# MultiboardV2.net
KiCad netlist of a schematic drawn in EAGLE
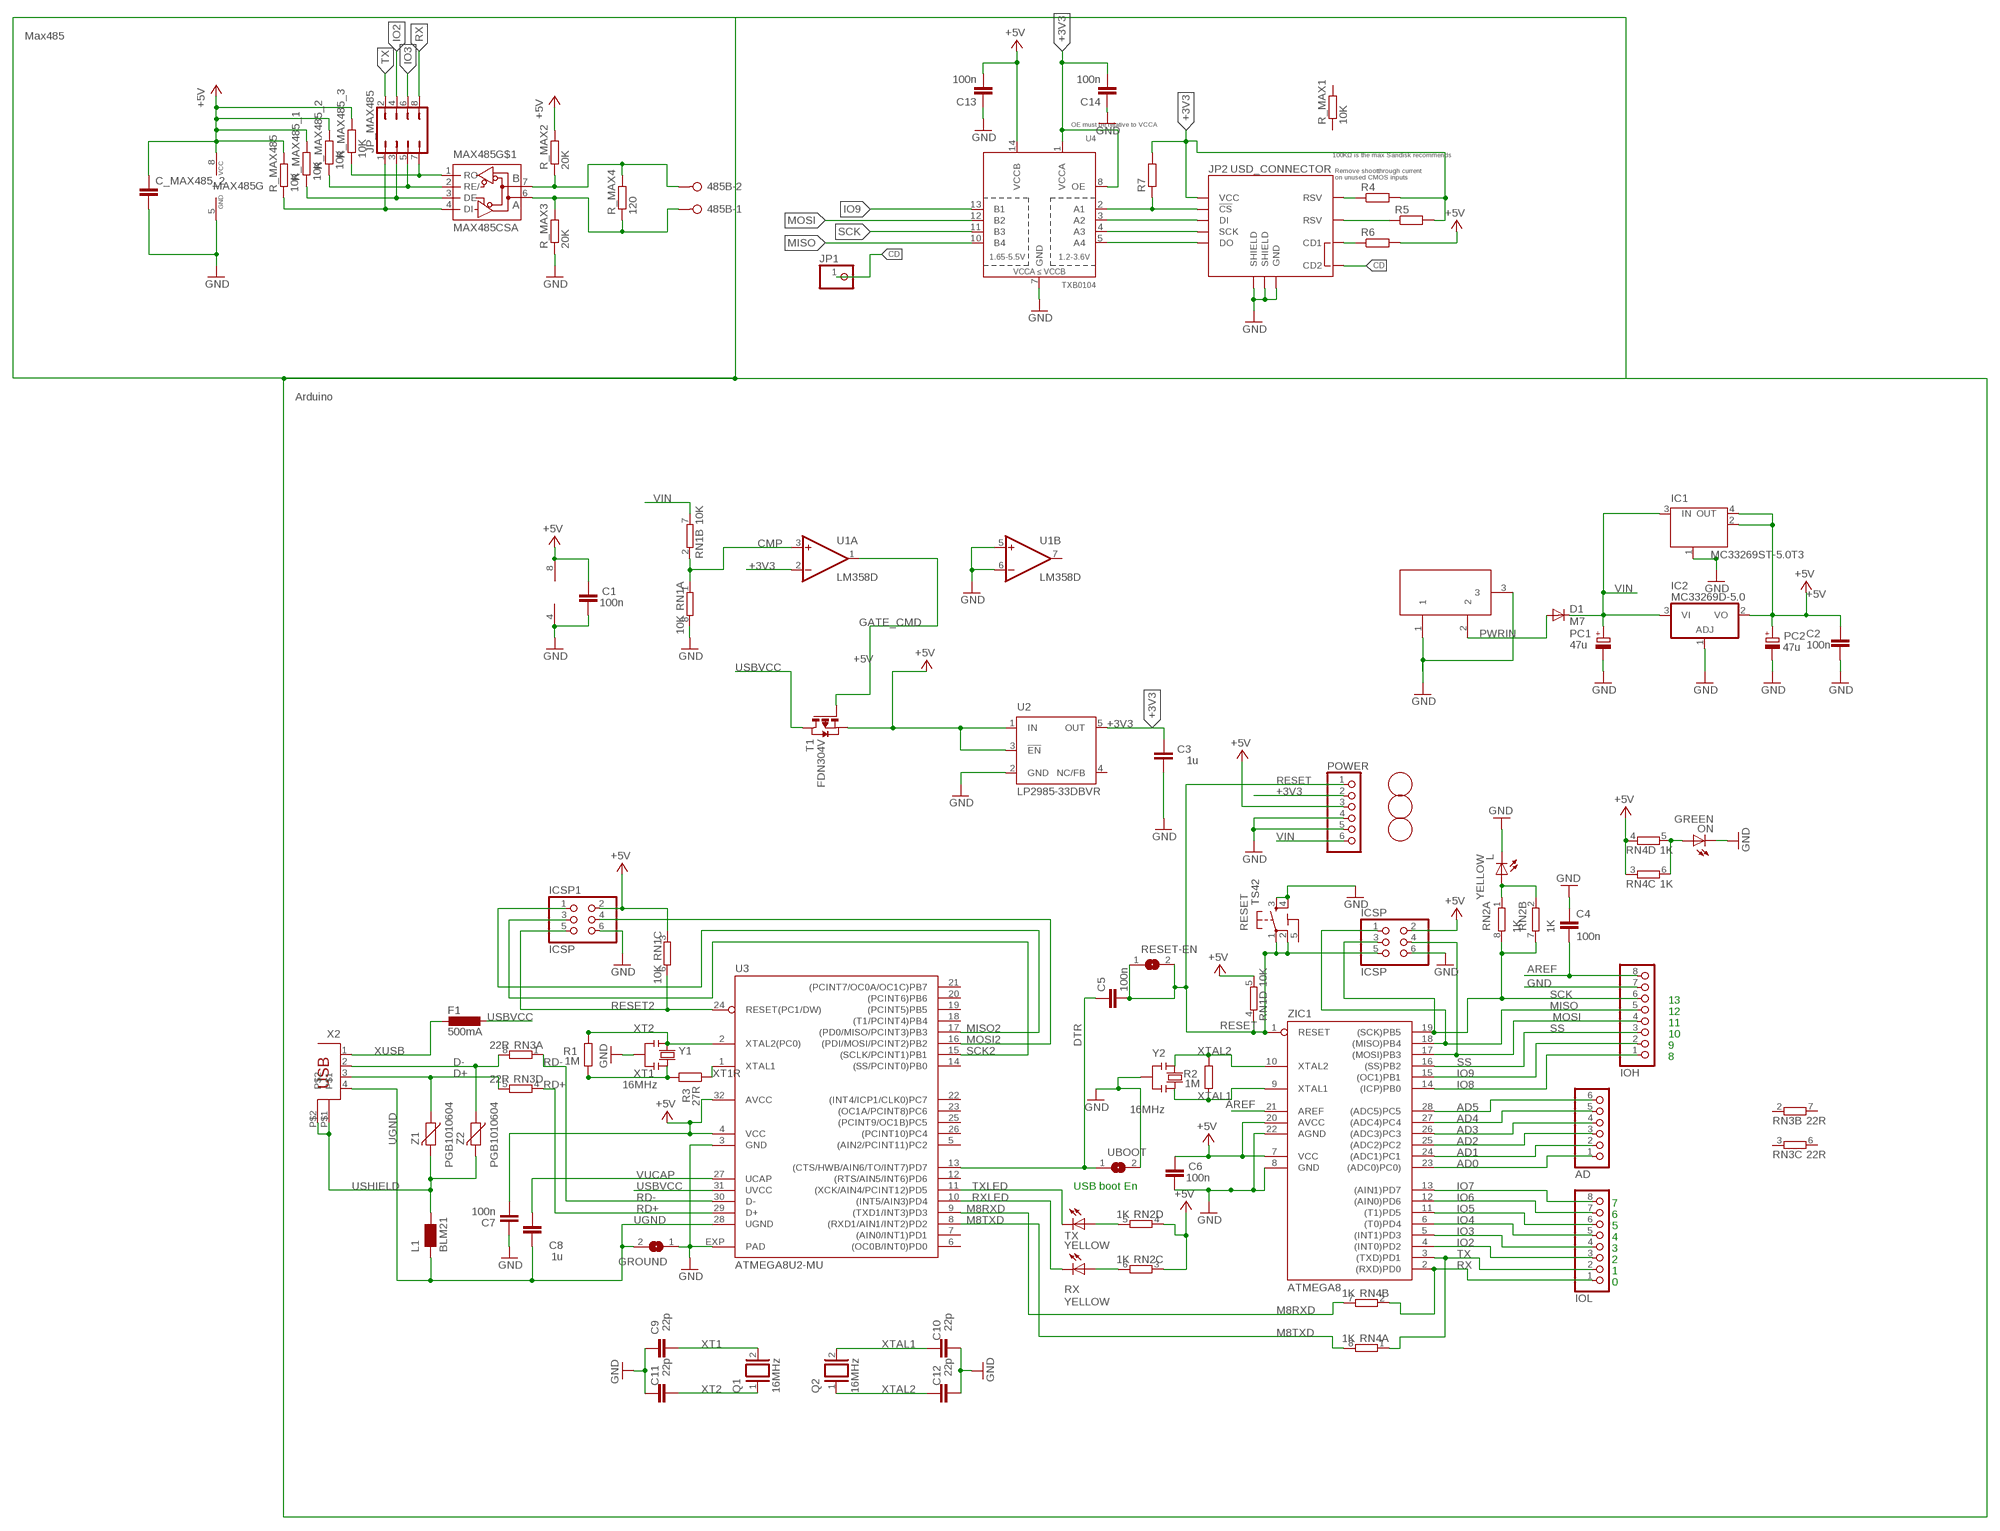
[diagram p0: schematic, sheet 1]

(export (version "E")
  (design (tool "Eeschema 10.0.6"))
  (components
    (comp (ref "485B")
      (value "W237-02P")
      (footprint "eagle-import:W237-132")
      (libsource (lib "eagle-import") (part "W237-02P"))
    )
    (comp (ref "AD")
      (value "PINHD-1X6")
      (footprint "eagle-import:1X06")
      (libsource (lib "eagle-import") (part "PINHD-1X6"))
    )
    (comp (ref "C1")
      (value "100n")
      (footprint "eagle-import:C0603-ROUND")
      (libsource (lib "eagle-import") (part "C-EU0603-RND"))
    )
    (comp (ref "C2")
      (value "100n")
      (footprint "eagle-import:C0603-ROUND")
      (libsource (lib "eagle-import") (part "C-EU0603-RND"))
    )
    (comp (ref "C3")
      (value "1u")
      (footprint "eagle-import:C0603-ROUND")
      (libsource (lib "eagle-import") (part "C-EU0603-RND"))
    )
    (comp (ref "C4")
      (value "100n")
      (footprint "eagle-import:C0603-ROUND")
      (libsource (lib "eagle-import") (part "C-EU0603-RND"))
    )
    (comp (ref "C5")
      (value "100n")
      (footprint "eagle-import:C0603-ROUND")
      (libsource (lib "eagle-import") (part "C-EU0603-RND"))
    )
    (comp (ref "C6")
      (value "100n")
      (footprint "eagle-import:C0603-ROUND")
      (libsource (lib "eagle-import") (part "C-EU0603-RND"))
    )
    (comp (ref "C7")
      (value "100n")
      (footprint "eagle-import:C0603-ROUND")
      (libsource (lib "eagle-import") (part "C-EU0603-RND"))
    )
    (comp (ref "C8")
      (value "1u")
      (footprint "eagle-import:C0603-ROUND")
      (libsource (lib "eagle-import") (part "C-EU0603-RND"))
    )
    (comp (ref "C9")
      (value "22p")
      (footprint "eagle-import:C0603-ROUND")
      (libsource (lib "eagle-import") (part "C-EU0603-RND"))
    )
    (comp (ref "C10")
      (value "22p")
      (footprint "eagle-import:C0603-ROUND")
      (libsource (lib "eagle-import") (part "C-EU0603-RND"))
    )
    (comp (ref "C11")
      (value "22p")
      (footprint "eagle-import:C0603-ROUND")
      (libsource (lib "eagle-import") (part "C-EU0603-RND"))
    )
    (comp (ref "C12")
      (value "22p")
      (footprint "eagle-import:C0603-ROUND")
      (libsource (lib "eagle-import") (part "C-EU0603-RND"))
    )
    (comp (ref "C13")
      (value "100n")
      (footprint "eagle-import:C0603-ROUND")
      (libsource (lib "eagle-import") (part "C-EU0603-RND"))
    )
    (comp (ref "C14")
      (value "100n")
      (footprint "eagle-import:C0603-ROUND")
      (libsource (lib "eagle-import") (part "C-EU0603-RND"))
    )
    (comp (ref "C_MAX485_2")
      (value "C-EUC0402")
      (footprint "eagle-import:C0402")
      (libsource (lib "eagle-import") (part "rcl_334_C-EUC0402"))
    )
    (comp (ref "D1")
      (value "M7")
      (footprint "eagle-import:SMB")
      (libsource (lib "eagle-import") (part "DIODE-SMB"))
    )
    (comp (ref "F1")
      (value "500mA")
      (footprint "eagle-import:L1812")
      (libsource (lib "eagle-import") (part "L-EUL1812"))
    )
    (comp (ref "GROUND")
      (value "SJ")
      (footprint "eagle-import:SJ")
      (libsource (lib "eagle-import") (part "SJ"))
    )
    (comp (ref "IC1")
      (value "MC33269ST-5.0T3")
      (footprint "eagle-import:SOT223")
      (libsource (lib "eagle-import") (part "MC33269ST-3.3T3"))
    )
    (comp (ref "IC2")
      (value "MC33269D-5.0")
      (footprint "eagle-import:DPACK")
      (libsource (lib "eagle-import") (part "MC33269?D-5.0"))
    )
    (comp (ref "ICSP")
      (value "ICSP")
      (footprint "eagle-import:2X03")
      (libsource (lib "eagle-import") (part "PINHD-2X3"))
    )
    (comp (ref "ICSP1")
      (value "ICSP")
      (footprint "eagle-import:2X03")
      (libsource (lib "eagle-import") (part "PINHD-2X3"))
    )
    (comp (ref "IOH")
      (value "PINHD-1X8")
      (footprint "eagle-import:1X08")
      (libsource (lib "eagle-import") (part "PINHD-1X8"))
    )
    (comp (ref "IOL")
      (value "PINHD-1X8")
      (footprint "eagle-import:1X08")
      (libsource (lib "eagle-import") (part "PINHD-1X8"))
    )
    (comp (ref "JP1")
      (value "PINHD-1X1")
      (footprint "eagle-import:1X01")
      (libsource (lib "eagle-import") (part "PINHD-1X1"))
    )
    (comp (ref "JP2")
      (value "USD_CONNECTOR")
      (footprint "eagle-import:MICRO-SD-SOCKET-PP")
      (libsource (lib "eagle-import") (part "USD_CONNECTOR"))
    )
    (comp (ref "JP_MAX485")
      (value "JP4Q")
      (footprint "eagle-import:JP4Q")
      (libsource (lib "eagle-import") (part "JP4Q"))
    )
    (comp (ref "L")
      (value "YELLOW")
      (footprint "eagle-import:CHIP-LED0805")
      (libsource (lib "eagle-import") (part "LEDCHIP-LED0805"))
    )
    (comp (ref "L1")
      (value "BLM21")
      (footprint "eagle-import:0805")
      (libsource (lib "eagle-import") (part "WE-CBF_0805"))
    )
    (comp (ref "MAX485")
      (value "MAX485CSA")
      (footprint "eagle-import:SO08")
      (libsource (lib "eagle-import") (part "MAX485CSA"))
    )
    (comp (ref "ON")
      (value "GREEN")
      (footprint "eagle-import:CHIP-LED0805")
      (libsource (lib "eagle-import") (part "LEDCHIP-LED0805"))
    )
    (comp (ref "PC1")
      (value "47u")
      (footprint "eagle-import:PANASONIC_D")
      (libsource (lib "eagle-import") (part "CPOL-EUD"))
    )
    (comp (ref "PC2")
      (value "47u")
      (footprint "eagle-import:PANASONIC_D")
      (libsource (lib "eagle-import") (part "CPOL-EUD"))
    )
    (comp (ref "POWER")
      (value "PINHD-1X6")
      (footprint "eagle-import:1X06")
      (libsource (lib "eagle-import") (part "PINHD-1X6"))
    )
    (comp (ref "Q1")
      (value "16MHz")
      (footprint "eagle-import:QS")
      (libsource (lib "eagle-import") (part "XTAL/S"))
    )
    (comp (ref "Q2")
      (value "16MHz")
      (footprint "eagle-import:QS")
      (libsource (lib "eagle-import") (part "XTAL/S"))
    )
    (comp (ref "R1")
      (value "1M")
      (footprint "eagle-import:R0603-ROUND")
      (libsource (lib "eagle-import") (part "R-EU_R0603"))
    )
    (comp (ref "R2")
      (value "1M")
      (footprint "eagle-import:R0603-ROUND")
      (libsource (lib "eagle-import") (part "R-EU_R0603"))
    )
    (comp (ref "R3")
      (value "27R")
      (footprint "eagle-import:R0603-ROUND")
      (libsource (lib "eagle-import") (part "R-EU_R0603"))
    )
    (comp (ref "R4")
      (value "100k")
      (footprint "eagle-import:R0402")
      (libsource (lib "eagle-import") (part "rcl_334_R-EU_R0402"))
    )
    (comp (ref "R5")
      (value "100k")
      (footprint "eagle-import:R0402")
      (libsource (lib "eagle-import") (part "rcl_334_R-EU_R0402"))
    )
    (comp (ref "R6")
      (value "100k")
      (footprint "eagle-import:R0402")
      (libsource (lib "eagle-import") (part "rcl_334_R-EU_R0402"))
    )
    (comp (ref "R7")
      (value "100k")
      (footprint "eagle-import:R0402")
      (libsource (lib "eagle-import") (part "rcl_334_R-EU_R0402"))
    )
    (comp (ref "RESET")
      (value "TS42")
      (footprint "eagle-import:TS42")
      (libsource (lib "eagle-import") (part "TS42"))
    )
    (comp (ref "RESET-EN")
      (value "SJ")
      (footprint "eagle-import:SJ")
      (libsource (lib "eagle-import") (part "SJ"))
    )
    (comp (ref "RN1")
      (value "10K")
      (footprint "eagle-import:CAY16")
      (libsource (lib "eagle-import") (part "4R-NCAY16"))
    )
    (comp (ref "RN2")
      (value "1K")
      (footprint "eagle-import:CAY16")
      (libsource (lib "eagle-import") (part "4R-NCAY16"))
    )
    (comp (ref "RN3")
      (value "22R")
      (footprint "eagle-import:CAY16")
      (libsource (lib "eagle-import") (part "4R-NCAY16"))
    )
    (comp (ref "RN4")
      (value "1K")
      (footprint "eagle-import:CAY16")
      (libsource (lib "eagle-import") (part "4R-NCAY16"))
    )
    (comp (ref "RX")
      (value "YELLOW")
      (footprint "eagle-import:CHIP-LED0805")
      (libsource (lib "eagle-import") (part "LEDCHIP-LED0805"))
    )
    (comp (ref "R_MAX1")
      (value "10K")
      (footprint "eagle-import:R0402")
      (libsource (lib "eagle-import") (part "rcl_334_R-EU_R0402"))
    )
    (comp (ref "R_MAX2")
      (value "20K")
      (footprint "eagle-import:R0402")
      (libsource (lib "eagle-import") (part "rcl_334_R-EU_R0402"))
    )
    (comp (ref "R_MAX3")
      (value "20K")
      (footprint "eagle-import:R0402")
      (libsource (lib "eagle-import") (part "rcl_334_R-EU_R0402"))
    )
    (comp (ref "R_MAX4")
      (value "120")
      (footprint "eagle-import:R0402")
      (libsource (lib "eagle-import") (part "rcl_334_R-EU_R0402"))
    )
    (comp (ref "R_MAX485")
      (value "10K")
      (footprint "eagle-import:R0402")
      (libsource (lib "eagle-import") (part "rcl_334_R-EU_R0402"))
    )
    (comp (ref "R_MAX485_1")
      (value "10K")
      (footprint "eagle-import:R0402")
      (libsource (lib "eagle-import") (part "rcl_334_R-EU_R0402"))
    )
    (comp (ref "R_MAX485_2")
      (value "10K")
      (footprint "eagle-import:R0402")
      (libsource (lib "eagle-import") (part "rcl_334_R-EU_R0402"))
    )
    (comp (ref "R_MAX485_3")
      (value "10K")
      (footprint "eagle-import:R0402")
      (libsource (lib "eagle-import") (part "rcl_334_R-EU_R0402"))
    )
    (comp (ref "T1")
      (value "FDN304V")
      (footprint "eagle-import:SOT-23")
      (libsource (lib "eagle-import") (part "PMOSSOT23"))
    )
    (comp (ref "TX")
      (value "YELLOW")
      (footprint "eagle-import:CHIP-LED0805")
      (libsource (lib "eagle-import") (part "LEDCHIP-LED0805"))
    )
    (comp (ref "U$3")
      (value "FIDUCIALMOUNT")
      (footprint "eagle-import:FIDUCIA-MOUNT")
      (libsource (lib "eagle-import") (part "FIDUCIALMOUNT"))
    )
    (comp (ref "U$4")
      (value "FIDUCIALMOUNT")
      (footprint "eagle-import:FIDUCIA-MOUNT")
      (libsource (lib "eagle-import") (part "FIDUCIALMOUNT"))
    )
    (comp (ref "U$6")
      (value "FIDUCIALMOUNT")
      (footprint "eagle-import:FIDUCIA-MOUNT")
      (libsource (lib "eagle-import") (part "FIDUCIALMOUNT"))
    )
    (comp (ref "U1")
      (value "LM358D")
      (footprint "eagle-import:SO08")
      (libsource (lib "eagle-import") (part "LM358D"))
    )
    (comp (ref "U2")
      (value "LP2985-33DBVR")
      (footprint "eagle-import:SOT23-DBV")
      (libsource (lib "eagle-import") (part "TPS77033"))
    )
    (comp (ref "U3")
      (value "ATMEGA8U2-MU")
      (footprint "eagle-import:QFN32")
      (libsource (lib "eagle-import") (part "ATMEGA8U2-MU"))
    )
    (comp (ref "U4")
      (value "TXB0104")
      (footprint "eagle-import:SO14")
      (libsource (lib "eagle-import") (part "TXB0104PWRSOIC14"))
    )
    (comp (ref "UBOOT")
      (value "SJ")
      (footprint "eagle-import:SJ")
      (libsource (lib "eagle-import") (part "SJ"))
    )
    (comp (ref "X1")
      (value "DC21MMX")
      (footprint "eagle-import:DC-21MM")
      (libsource (lib "eagle-import") (part "DC21MMX"))
    )
    (comp (ref "X2")
      (value "PN61729")
      (footprint "eagle-import:PN61729")
      (libsource (lib "eagle-import") (part "PN61729"))
    )
    (comp (ref "Y1")
      (value "16MHz")
      (footprint "eagle-import:RESONATOR")
      (libsource (lib "eagle-import") (part "RESONATORMU"))
    )
    (comp (ref "Y2")
      (value "16MHz")
      (footprint "eagle-import:RESONATOR")
      (libsource (lib "eagle-import") (part "RESONATORMU"))
    )
    (comp (ref "Z1")
      (value "PGB1010604")
      (footprint "eagle-import:CT_CN0603")
      (libsource (lib "eagle-import") (part "VARISTORCN0603"))
    )
    (comp (ref "Z2")
      (value "PGB1010604")
      (footprint "eagle-import:CT_CN0603")
      (libsource (lib "eagle-import") (part "VARISTORCN0603"))
    )
    (comp (ref "ZIC1")
      (value "ATMEGA8")
      (footprint "eagle-import:DIL28-3")
      (libsource (lib "eagle-import") (part "AT90S4433P"))
    )
  )
  (nets
    (net (code "1") (name "+3V3") (class "Default")
      (node (ref "C14") (pin "2") (pinfunction "2_2") (pintype "passive"))
      (node (ref "C3") (pin "2") (pinfunction "2_2") (pintype "passive"))
      (node (ref "JP2") (pin "VCC") (pinfunction "VCC_VCC") (pintype "bidirectional"))
      (node (ref "POWER") (pin "2") (pinfunction "2_2") (pintype "passive"))
      (node (ref "R4") (pin "2") (pinfunction "2_2") (pintype "passive"))
      (node (ref "R5") (pin "2") (pinfunction "2_2") (pintype "passive"))
      (node (ref "R7") (pin "2") (pinfunction "2_2") (pintype "passive"))
      (node (ref "U1") (pin "2") (pinfunction "-IN_2") (pintype "input"))
      (node (ref "U2") (pin "5") (pinfunction "OUT_5") (pintype "passive"))
      (node (ref "U4") (pin "1") (pinfunction "VCCA_1") (pintype "bidirectional"))
      (node (ref "U4") (pin "8") (pinfunction "OE_8") (pintype "bidirectional"))
    )
    (net (code "2") (name "+5V") (class "Default")
      (node (ref "C1") (pin "2") (pinfunction "2_2") (pintype "passive"))
      (node (ref "C13") (pin "2") (pinfunction "2_2") (pintype "passive"))
      (node (ref "C2") (pin "2") (pinfunction "2_2") (pintype "passive"))
      (node (ref "C6") (pin "2") (pinfunction "2_2") (pintype "passive"))
      (node (ref "C7") (pin "1") (pinfunction "1_1") (pintype "passive"))
      (node (ref "C_MAX485_2") (pin "1") (pinfunction "1_1") (pintype "passive"))
      (node (ref "IC1") (pin "2") (pinfunction "OUT_2") (pintype "passive"))
      (node (ref "IC1") (pin "4") (pinfunction "OUT_4") (pintype "passive"))
      (node (ref "IC2") (pin "2") (pinfunction "VO_2") (pintype "passive"))
      (node (ref "ICSP") (pin "2") (pinfunction "2_2") (pintype "passive"))
      (node (ref "ICSP1") (pin "2") (pinfunction "2_2") (pintype "passive"))
      (node (ref "MAX485") (pin "8") (pinfunction "VCC_8") (pintype "power_in"))
      (node (ref "PC2") (pin "+") (pinfunction "+_+") (pintype "passive"))
      (node (ref "POWER") (pin "3") (pinfunction "3_3") (pintype "passive"))
      (node (ref "R6") (pin "2") (pinfunction "2_2") (pintype "passive"))
      (node (ref "RN1") (pin "3") (pinfunction "1_3") (pintype "passive"))
      (node (ref "RN1") (pin "5") (pinfunction "2_5") (pintype "passive"))
      (node (ref "RN2") (pin "3") (pinfunction "1_3") (pintype "passive"))
      (node (ref "RN2") (pin "4") (pinfunction "1_4") (pintype "passive"))
      (node (ref "RN4") (pin "3") (pinfunction "1_3") (pintype "passive"))
      (node (ref "RN4") (pin "4") (pinfunction "1_4") (pintype "passive"))
      (node (ref "R_MAX2") (pin "2") (pinfunction "2_2") (pintype "passive"))
      (node (ref "R_MAX485") (pin "2") (pinfunction "2_2") (pintype "passive"))
      (node (ref "R_MAX485_1") (pin "2") (pinfunction "2_2") (pintype "passive"))
      (node (ref "R_MAX485_2") (pin "2") (pinfunction "2_2") (pintype "passive"))
      (node (ref "R_MAX485_3") (pin "2") (pinfunction "2_2") (pintype "passive"))
      (node (ref "T1") (pin "2") (pinfunction "S_2") (pintype "passive"))
      (node (ref "U1") (pin "8") (pinfunction "V+_8") (pintype "power_in"))
      (node (ref "U2") (pin "1") (pinfunction "IN_1") (pintype "input"))
      (node (ref "U2") (pin "3") (pinfunction "~{EN}_3") (pintype "input"))
      (node (ref "U3") (pin "32") (pinfunction "AVCC_32") (pintype "power_in"))
      (node (ref "U3") (pin "4") (pinfunction "VCC_4") (pintype "power_in"))
      (node (ref "U4") (pin "14") (pinfunction "VCCB_14") (pintype "bidirectional"))
      (node (ref "ZIC1") (pin "20") (pinfunction "AVCC_20") (pintype "power_in"))
      (node (ref "ZIC1") (pin "7") (pinfunction "VCC_7") (pintype "power_in"))
    )
    (net (code "3") (name "/5-GND") (class "Default")
      (node (ref "RESET") (pin "5") (pinfunction "5-GND_5") (pintype "power_in"))
    )
    (net (code "4") (name "/AD0") (class "Default")
      (node (ref "AD") (pin "1") (pinfunction "1_1") (pintype "passive"))
      (node (ref "ZIC1") (pin "23") (pinfunction "(ADC0)PC0)_23") (pintype "bidirectional"))
    )
    (net (code "5") (name "/AD1") (class "Default")
      (node (ref "AD") (pin "2") (pinfunction "2_2") (pintype "passive"))
      (node (ref "ZIC1") (pin "24") (pinfunction "(ADC1)PC1_24") (pintype "bidirectional"))
    )
    (net (code "6") (name "/AD2") (class "Default")
      (node (ref "AD") (pin "3") (pinfunction "3_3") (pintype "passive"))
      (node (ref "ZIC1") (pin "25") (pinfunction "(ADC2)PC2_25") (pintype "bidirectional"))
    )
    (net (code "7") (name "/AD3") (class "Default")
      (node (ref "AD") (pin "4") (pinfunction "4_4") (pintype "passive"))
      (node (ref "ZIC1") (pin "26") (pinfunction "(ADC3)PC3_26") (pintype "bidirectional"))
    )
    (net (code "8") (name "/AD4") (class "Default")
      (node (ref "AD") (pin "5") (pinfunction "5_5") (pintype "passive"))
      (node (ref "ZIC1") (pin "27") (pinfunction "(ADC4)PC4_27") (pintype "bidirectional"))
    )
    (net (code "9") (name "/AD5") (class "Default")
      (node (ref "AD") (pin "6") (pinfunction "6_6") (pintype "passive"))
      (node (ref "ZIC1") (pin "28") (pinfunction "(ADC5)PC5_28") (pintype "bidirectional"))
    )
    (net (code "10") (name "/AREF") (class "Default")
      (node (ref "C4") (pin "2") (pinfunction "2_2") (pintype "passive"))
      (node (ref "IOH") (pin "8") (pinfunction "8_8") (pintype "passive"))
      (node (ref "ZIC1") (pin "21") (pinfunction "AREF_21") (pintype "passive"))
    )
    (net (code "11") (name "/CMP") (class "Default")
      (node (ref "RN1") (pin "1") (pinfunction "1_1") (pintype "passive"))
      (node (ref "RN1") (pin "2") (pinfunction "1_2") (pintype "passive"))
      (node (ref "U1") (pin "3") (pinfunction "+IN_3") (pintype "input"))
    )
    (net (code "12") (name "/D+") (class "Default")
      (node (ref "RN3") (pin "5") (pinfunction "2_5") (pintype "passive"))
      (node (ref "X2") (pin "3") (pinfunction "3_3") (pintype "bidirectional"))
      (node (ref "Z1") (pin "1") (pinfunction "1_1") (pintype "passive"))
    )
    (net (code "13") (name "/D-") (class "Default")
      (node (ref "RN3") (pin "8") (pinfunction "2_8") (pintype "passive"))
      (node (ref "X2") (pin "2") (pinfunction "2_2") (pintype "bidirectional"))
      (node (ref "Z2") (pin "1") (pinfunction "1_1") (pintype "passive"))
    )
    (net (code "14") (name "/DTR") (class "Default")
      (node (ref "C5") (pin "1") (pinfunction "1_1") (pintype "passive"))
      (node (ref "U3") (pin "13") (pinfunction "(CTS/HWB/AIN6/TO/INT7)PD7_13") (pintype "bidirectional"))
      (node (ref "UBOOT") (pin "1") (pinfunction "1_1") (pintype "passive"))
    )
    (net (code "15") (name "/GATE_CMD") (class "Default")
      (node (ref "T1") (pin "3") (pinfunction "G_3") (pintype "passive"))
      (node (ref "U1") (pin "1") (pinfunction "OUT_1") (pintype "output"))
    )
    (net (code "16") (name "/IO4") (class "Default")
      (node (ref "IOL") (pin "5") (pinfunction "5_5") (pintype "passive"))
      (node (ref "ZIC1") (pin "6") (pinfunction "(T0)PD4_6") (pintype "bidirectional"))
    )
    (net (code "17") (name "/IO5") (class "Default")
      (node (ref "IOL") (pin "6") (pinfunction "6_6") (pintype "passive"))
      (node (ref "ZIC1") (pin "11") (pinfunction "(T1)PD5_11") (pintype "bidirectional"))
    )
    (net (code "18") (name "/IO6") (class "Default")
      (node (ref "IOL") (pin "7") (pinfunction "7_7") (pintype "passive"))
      (node (ref "ZIC1") (pin "12") (pinfunction "(AIN0)PD6_12") (pintype "bidirectional"))
    )
    (net (code "19") (name "/IO7") (class "Default")
      (node (ref "IOL") (pin "8") (pinfunction "8_8") (pintype "passive"))
      (node (ref "ZIC1") (pin "13") (pinfunction "(AIN1)PD7_13") (pintype "bidirectional"))
    )
    (net (code "20") (name "/IO8") (class "Default")
      (node (ref "IOH") (pin "1") (pinfunction "1_1") (pintype "passive"))
      (node (ref "ZIC1") (pin "14") (pinfunction "(ICP)PB0_14") (pintype "bidirectional"))
    )
    (net (code "21") (name "/M8RXD") (class "Default")
      (node (ref "RN4") (pin "7") (pinfunction "2_7") (pintype "passive"))
      (node (ref "U3") (pin "9") (pinfunction "(TXD1/INT3)PD3_9") (pintype "bidirectional"))
    )
    (net (code "22") (name "/M8TXD") (class "Default")
      (node (ref "RN4") (pin "8") (pinfunction "2_8") (pintype "passive"))
      (node (ref "U3") (pin "8") (pinfunction "(RXD1/AIN1/INT2)PD2_8") (pintype "bidirectional"))
    )
    (net (code "23") (name "/MISO2") (class "Default")
      (node (ref "ICSP1") (pin "1") (pinfunction "1_1") (pintype "passive"))
      (node (ref "U3") (pin "17") (pinfunction "(PD0/MISO/PCINT3)PB3_17") (pintype "bidirectional"))
    )
    (net (code "24") (name "/MOSI2") (class "Default")
      (node (ref "ICSP1") (pin "4") (pinfunction "4_4") (pintype "passive"))
      (node (ref "U3") (pin "16") (pinfunction "(PDI/MOSI/PCINT2)PB2_16") (pintype "bidirectional"))
    )
    (net (code "25") (name "/PWRIN") (class "Default")
      (node (ref "D1") (pin "A") (pinfunction "A_A") (pintype "passive"))
      (node (ref "X1") (pin "2") (pinfunction "2_2") (pintype "power_in"))
    )
    (net (code "26") (name "/RD+") (class "Default")
      (node (ref "RN3") (pin "4") (pinfunction "1_4") (pintype "passive"))
      (node (ref "U3") (pin "29") (pinfunction "D+_29") (pintype "bidirectional"))
    )
    (net (code "27") (name "/RD-") (class "Default")
      (node (ref "RN3") (pin "1") (pinfunction "1_1") (pintype "passive"))
      (node (ref "U3") (pin "30") (pinfunction "D-_30") (pintype "bidirectional"))
    )
    (net (code "28") (name "/RESET") (class "Default")
      (node (ref "C5") (pin "2") (pinfunction "2_2") (pintype "passive"))
      (node (ref "ICSP") (pin "5") (pinfunction "5_5") (pintype "passive"))
      (node (ref "POWER") (pin "1") (pinfunction "1_1") (pintype "passive"))
      (node (ref "RESET") (pin "1") (pinfunction "1_1") (pintype "passive"))
      (node (ref "RESET") (pin "2") (pinfunction "2_2") (pintype "passive"))
      (node (ref "RESET-EN") (pin "1") (pinfunction "1_1") (pintype "passive"))
      (node (ref "RESET-EN") (pin "2") (pinfunction "2_2") (pintype "passive"))
      (node (ref "RN1") (pin "4") (pinfunction "1_4") (pintype "passive"))
      (node (ref "ZIC1") (pin "1") (pinfunction "RESET_1") (pintype "input"))
    )
    (net (code "29") (name "/RESET2") (class "Default")
      (node (ref "ICSP1") (pin "5") (pinfunction "5_5") (pintype "passive"))
      (node (ref "RN1") (pin "6") (pinfunction "2_6") (pintype "passive"))
      (node (ref "U3") (pin "24") (pinfunction "RESET(PC1/DW)_24") (pintype "input"))
    )
    (net (code "30") (name "/RXLED") (class "Default")
      (node (ref "RX") (pin "C") (pinfunction "C_C") (pintype "passive"))
      (node (ref "U3") (pin "10") (pinfunction "(INT5/AIN3)PD4_10") (pintype "bidirectional"))
    )
    (net (code "31") (name "/SCK2") (class "Default")
      (node (ref "ICSP1") (pin "3") (pinfunction "3_3") (pintype "passive"))
      (node (ref "U3") (pin "15") (pinfunction "(SCLK/PCINT1)PB1_15") (pintype "bidirectional"))
    )
    (net (code "32") (name "/SS") (class "Default")
      (node (ref "IOH") (pin "3") (pinfunction "3_3") (pintype "passive"))
      (node (ref "ZIC1") (pin "16") (pinfunction "(SS)PB2_16") (pintype "bidirectional"))
    )
    (net (code "33") (name "/TXLED") (class "Default")
      (node (ref "TX") (pin "C") (pinfunction "C_C") (pintype "passive"))
      (node (ref "U3") (pin "11") (pinfunction "(XCK/AIN4/PCINT12)PD5_11") (pintype "bidirectional"))
    )
    (net (code "34") (name "/UGND") (class "Default")
      (node (ref "C8") (pin "2") (pinfunction "2_2") (pintype "passive"))
      (node (ref "GROUND") (pin "2") (pinfunction "2_2") (pintype "passive"))
      (node (ref "L1") (pin "1") (pinfunction "1_1") (pintype "passive"))
      (node (ref "U3") (pin "28") (pinfunction "UGND_28") (pintype "power_in"))
      (node (ref "X2") (pin "4") (pinfunction "4_4") (pintype "bidirectional"))
    )
    (net (code "35") (name "/USBVCC") (class "Default")
      (node (ref "F1") (pin "1") (pinfunction "1_1") (pintype "passive"))
      (node (ref "T1") (pin "1") (pinfunction "D_1") (pintype "passive"))
      (node (ref "U3") (pin "31") (pinfunction "UVCC_31") (pintype "power_in"))
    )
    (net (code "36") (name "/USHIELD") (class "Default")
      (node (ref "L1") (pin "2") (pinfunction "2_2") (pintype "passive"))
      (node (ref "X2") (pin "P$1") (pinfunction "P$1_P$1") (pintype "bidirectional"))
      (node (ref "X2") (pin "P$2") (pinfunction "P$2_P$2") (pintype "bidirectional"))
      (node (ref "Z1") (pin "2") (pinfunction "2_2") (pintype "passive"))
      (node (ref "Z2") (pin "2") (pinfunction "2_2") (pintype "passive"))
    )
    (net (code "37") (name "/VIN") (class "Default")
      (node (ref "D1") (pin "C") (pinfunction "C_C") (pintype "passive"))
      (node (ref "IC1") (pin "3") (pinfunction "IN_3") (pintype "input"))
      (node (ref "IC2") (pin "3") (pinfunction "VI_3") (pintype "input"))
      (node (ref "PC1") (pin "+") (pinfunction "+_+") (pintype "passive"))
      (node (ref "POWER") (pin "6") (pinfunction "6_6") (pintype "passive"))
      (node (ref "RN1") (pin "7") (pinfunction "2_7") (pintype "passive"))
    )
    (net (code "38") (name "/VUCAP") (class "Default")
      (node (ref "C8") (pin "1") (pinfunction "1_1") (pintype "passive"))
      (node (ref "U3") (pin "27") (pinfunction "UCAP_27") (pintype "passive"))
    )
    (net (code "39") (name "/XT1") (class "Default")
      (node (ref "C9") (pin "1") (pinfunction "1_1") (pintype "passive"))
      (node (ref "Q1") (pin "2") (pinfunction "2_2") (pintype "passive"))
      (node (ref "R1") (pin "1") (pinfunction "1_1") (pintype "passive"))
      (node (ref "R3") (pin "2") (pinfunction "2_2") (pintype "passive"))
      (node (ref "Y1") (pin "3") (pinfunction "3_3") (pintype "passive"))
    )
    (net (code "40") (name "/XT1R") (class "Default")
      (node (ref "R3") (pin "1") (pinfunction "1_1") (pintype "passive"))
      (node (ref "U3") (pin "1") (pinfunction "XTAL1_1") (pintype "bidirectional"))
    )
    (net (code "41") (name "/XT2") (class "Default")
      (node (ref "C11") (pin "1") (pinfunction "1_1") (pintype "passive"))
      (node (ref "Q1") (pin "1") (pinfunction "1_1") (pintype "passive"))
      (node (ref "R1") (pin "2") (pinfunction "2_2") (pintype "passive"))
      (node (ref "U3") (pin "2") (pinfunction "XTAL2(PC0)_2") (pintype "bidirectional"))
      (node (ref "Y1") (pin "1") (pinfunction "1_1") (pintype "passive"))
    )
    (net (code "42") (name "/XTAL1") (class "Default")
      (node (ref "C10") (pin "2") (pinfunction "2_2") (pintype "passive"))
      (node (ref "Q2") (pin "2") (pinfunction "2_2") (pintype "passive"))
      (node (ref "R2") (pin "1") (pinfunction "1_1") (pintype "passive"))
      (node (ref "Y2") (pin "3") (pinfunction "3_3") (pintype "passive"))
      (node (ref "ZIC1") (pin "9") (pinfunction "XTAL1_9") (pintype "bidirectional"))
    )
    (net (code "43") (name "/XTAL2") (class "Default")
      (node (ref "C12") (pin "2") (pinfunction "2_2") (pintype "passive"))
      (node (ref "Q2") (pin "1") (pinfunction "1_1") (pintype "passive"))
      (node (ref "R2") (pin "2") (pinfunction "2_2") (pintype "passive"))
      (node (ref "Y2") (pin "1") (pinfunction "1_1") (pintype "passive"))
      (node (ref "ZIC1") (pin "10") (pinfunction "XTAL2_10") (pintype "bidirectional"))
    )
    (net (code "44") (name "/XUSB") (class "Default")
      (node (ref "F1") (pin "2") (pinfunction "2_2") (pintype "passive"))
      (node (ref "X2") (pin "1") (pinfunction "1_1") (pintype "bidirectional"))
    )
    (net (code "45") (name "CD") (class "Default")
      (node (ref "JP1") (pin "1") (pinfunction "1_1") (pintype "passive"))
      (node (ref "JP2") (pin "CD2") (pinfunction "CD2_CD2") (pintype "bidirectional"))
    )
    (net (code "46") (name "GND") (class "Default")
      (node (ref "C1") (pin "1") (pinfunction "1_1") (pintype "passive"))
      (node (ref "C10") (pin "1") (pinfunction "1_1") (pintype "passive"))
      (node (ref "C11") (pin "2") (pinfunction "2_2") (pintype "passive"))
      (node (ref "C12") (pin "1") (pinfunction "1_1") (pintype "passive"))
      (node (ref "C13") (pin "1") (pinfunction "1_1") (pintype "passive"))
      (node (ref "C14") (pin "1") (pinfunction "1_1") (pintype "passive"))
      (node (ref "C2") (pin "1") (pinfunction "1_1") (pintype "passive"))
      (node (ref "C3") (pin "1") (pinfunction "1_1") (pintype "passive"))
      (node (ref "C4") (pin "1") (pinfunction "1_1") (pintype "passive"))
      (node (ref "C6") (pin "1") (pinfunction "1_1") (pintype "passive"))
      (node (ref "C7") (pin "2") (pinfunction "2_2") (pintype "passive"))
      (node (ref "C9") (pin "2") (pinfunction "2_2") (pintype "passive"))
      (node (ref "C_MAX485_2") (pin "2") (pinfunction "2_2") (pintype "passive"))
      (node (ref "GROUND") (pin "1") (pinfunction "1_1") (pintype "passive"))
      (node (ref "IC1") (pin "1") (pinfunction "GND/ADJ_1") (pintype "input"))
      (node (ref "IC2") (pin "1") (pinfunction "ADJ_1") (pintype "input"))
      (node (ref "ICSP") (pin "6") (pinfunction "6_6") (pintype "passive"))
      (node (ref "ICSP1") (pin "6") (pinfunction "6_6") (pintype "passive"))
      (node (ref "IOH") (pin "7") (pinfunction "7_7") (pintype "passive"))
      (node (ref "JP2") (pin "GND") (pinfunction "GND_GND") (pintype "bidirectional"))
      (node (ref "JP2") (pin "GND1") (pinfunction "SHIELD_GND1") (pintype "bidirectional"))
      (node (ref "JP2") (pin "GND3") (pinfunction "SHIELD_GND3") (pintype "bidirectional"))
      (node (ref "L") (pin "C") (pinfunction "C_C") (pintype "passive"))
      (node (ref "MAX485") (pin "5") (pinfunction "GND_5") (pintype "power_in"))
      (node (ref "ON") (pin "C") (pinfunction "C_C") (pintype "passive"))
      (node (ref "PC1") (pin "-") (pinfunction "-_-") (pintype "passive"))
      (node (ref "PC2") (pin "-") (pinfunction "-_-") (pintype "passive"))
      (node (ref "POWER") (pin "4") (pinfunction "4_4") (pintype "passive"))
      (node (ref "POWER") (pin "5") (pinfunction "5_5") (pintype "passive"))
      (node (ref "RESET") (pin "3") (pinfunction "3_3") (pintype "passive"))
      (node (ref "RESET") (pin "4") (pinfunction "4_4") (pintype "passive"))
      (node (ref "RN1") (pin "8") (pinfunction "2_8") (pintype "passive"))
      (node (ref "R_MAX3") (pin "1") (pinfunction "1_1") (pintype "passive"))
      (node (ref "U1") (pin "4") (pinfunction "V-_4") (pintype "power_in"))
      (node (ref "U1") (pin "5") (pinfunction "+IN_5") (pintype "input"))
      (node (ref "U1") (pin "6") (pinfunction "-IN_6") (pintype "input"))
      (node (ref "U2") (pin "2") (pinfunction "GND_2") (pintype "power_in"))
      (node (ref "U3") (pin "3") (pinfunction "GND_3") (pintype "power_in"))
      (node (ref "U3") (pin "EXP") (pinfunction "PAD_EXP") (pintype "power_in"))
      (node (ref "U4") (pin "7") (pinfunction "GND_7") (pintype "bidirectional"))
      (node (ref "UBOOT") (pin "2") (pinfunction "2_2") (pintype "passive"))
      (node (ref "X1") (pin "1") (pinfunction "1_1") (pintype "power_in"))
      (node (ref "X1") (pin "3") (pinfunction "3_3") (pintype "power_in"))
      (node (ref "Y1") (pin "2") (pinfunction "2_2") (pintype "passive"))
      (node (ref "Y2") (pin "2") (pinfunction "2_2") (pintype "passive"))
      (node (ref "ZIC1") (pin "22") (pinfunction "AGND_22") (pintype "power_in"))
      (node (ref "ZIC1") (pin "8") (pinfunction "GND_8") (pintype "power_in"))
    )
    (net (code "47") (name "IO2") (class "Default")
      (node (ref "IOL") (pin "3") (pinfunction "3_3") (pintype "passive"))
      (node (ref "JP_MAX485") (pin "4") (pinfunction "4_4") (pintype "passive"))
      (node (ref "ZIC1") (pin "4") (pinfunction "(INT0)PD2_4") (pintype "bidirectional"))
    )
    (net (code "48") (name "IO3") (class "Default")
      (node (ref "IOL") (pin "4") (pinfunction "4_4") (pintype "passive"))
      (node (ref "JP_MAX485") (pin "6") (pinfunction "6_6") (pintype "passive"))
      (node (ref "ZIC1") (pin "5") (pinfunction "(INT1)PD3_5") (pintype "bidirectional"))
    )
    (net (code "49") (name "IO9") (class "Default")
      (node (ref "IOH") (pin "2") (pinfunction "2_2") (pintype "passive"))
      (node (ref "U4") (pin "13") (pinfunction "B1_13") (pintype "bidirectional"))
      (node (ref "ZIC1") (pin "15") (pinfunction "(OC1)PB1_15") (pintype "bidirectional"))
    )
    (net (code "50") (name "MISO") (class "Default")
      (node (ref "ICSP") (pin "1") (pinfunction "1_1") (pintype "passive"))
      (node (ref "IOH") (pin "5") (pinfunction "5_5") (pintype "passive"))
      (node (ref "U4") (pin "10") (pinfunction "B4_10") (pintype "bidirectional"))
      (node (ref "ZIC1") (pin "18") (pinfunction "(MISO)PB4_18") (pintype "bidirectional"))
    )
    (net (code "51") (name "MOSI") (class "Default")
      (node (ref "ICSP") (pin "4") (pinfunction "4_4") (pintype "passive"))
      (node (ref "IOH") (pin "4") (pinfunction "4_4") (pintype "passive"))
      (node (ref "U4") (pin "12") (pinfunction "B2_12") (pintype "bidirectional"))
      (node (ref "ZIC1") (pin "17") (pinfunction "(MOSI)PB3_17") (pintype "bidirectional"))
    )
    (net (code "52") (name "Net-(485BA-KL)") (class "Default")
      (node (ref "485B") (pin "1") (pinfunction "KL_1") (pintype "passive"))
      (node (ref "MAX485") (pin "6") (pinfunction "A_6") (pintype "passive"))
      (node (ref "R_MAX3") (pin "2") (pinfunction "2_2") (pintype "passive"))
      (node (ref "R_MAX4") (pin "1") (pinfunction "1_1") (pintype "passive"))
    )
    (net (code "53") (name "Net-(485BB-KL)") (class "Default")
      (node (ref "485B") (pin "2") (pinfunction "KL_2") (pintype "passive"))
      (node (ref "MAX485") (pin "7") (pinfunction "B_7") (pintype "passive"))
      (node (ref "R_MAX2") (pin "1") (pinfunction "1_1") (pintype "passive"))
      (node (ref "R_MAX4") (pin "2") (pinfunction "2_2") (pintype "passive"))
    )
    (net (code "54") (name "Net-(JP2-PadCD1)") (class "Default")
      (node (ref "JP2") (pin "CD1") (pinfunction "CD1_CD1") (pintype "bidirectional"))
      (node (ref "R6") (pin "1") (pinfunction "1_1") (pintype "passive"))
    )
    (net (code "55") (name "Net-(JP2-RSV-PadRSV1)") (class "Default")
      (node (ref "JP2") (pin "RSV1") (pinfunction "RSV_RSV1") (pintype "bidirectional"))
      (node (ref "R4") (pin "1") (pinfunction "1_1") (pintype "passive"))
    )
    (net (code "56") (name "Net-(JP2-RSV-PadRSV2)") (class "Default")
      (node (ref "JP2") (pin "RSV2") (pinfunction "RSV_RSV2") (pintype "bidirectional"))
      (node (ref "R5") (pin "1") (pinfunction "1_1") (pintype "passive"))
    )
    (net (code "57") (name "Net-(JP2-SCK)") (class "Default")
      (node (ref "JP2") (pin "SCLK") (pinfunction "SCK_SCLK") (pintype "bidirectional"))
      (node (ref "U4") (pin "4") (pinfunction "A3_4") (pintype "bidirectional"))
    )
    (net (code "58") (name "Net-(JP2-~{CS})") (class "Default")
      (node (ref "JP2") (pin "CS") (pinfunction "~{CS}_CS") (pintype "bidirectional"))
      (node (ref "R7") (pin "1") (pinfunction "1_1") (pintype "passive"))
      (node (ref "U4") (pin "2") (pinfunction "A1_2") (pintype "bidirectional"))
    )
    (net (code "59") (name "Net-(MAX485B-DE)") (class "Default")
      (node (ref "JP_MAX485") (pin "3") (pinfunction "3_3") (pintype "passive"))
      (node (ref "MAX485") (pin "3") (pinfunction "DE_3") (pintype "input"))
      (node (ref "R_MAX485_1") (pin "1") (pinfunction "1_1") (pintype "passive"))
    )
    (net (code "60") (name "Net-(MAX485B-DI)") (class "Default")
      (node (ref "JP_MAX485") (pin "1") (pinfunction "1_1") (pintype "passive"))
      (node (ref "MAX485") (pin "4") (pinfunction "DI_4") (pintype "input"))
      (node (ref "R_MAX485") (pin "1") (pinfunction "1_1") (pintype "passive"))
    )
    (net (code "61") (name "Net-(MAX485B-RE{slash})") (class "Default")
      (node (ref "JP_MAX485") (pin "5") (pinfunction "5_5") (pintype "passive"))
      (node (ref "MAX485") (pin "2") (pinfunction "RE/_2") (pintype "input"))
      (node (ref "R_MAX485_2") (pin "1") (pinfunction "1_1") (pintype "passive"))
    )
    (net (code "62") (name "Net-(MAX485B-RO)") (class "Default")
      (node (ref "JP_MAX485") (pin "7") (pinfunction "7_7") (pintype "passive"))
      (node (ref "MAX485") (pin "1") (pinfunction "RO_1") (pintype "output"))
      (node (ref "R_MAX485_3") (pin "1") (pinfunction "1_1") (pintype "passive"))
    )
    (net (code "63") (name "Net-(RN2B-1)") (class "Default")
      (node (ref "L") (pin "A") (pinfunction "A_A") (pintype "passive"))
      (node (ref "RN2") (pin "1") (pinfunction "1_1") (pintype "passive"))
      (node (ref "RN2") (pin "2") (pinfunction "1_2") (pintype "passive"))
    )
    (net (code "64") (name "Net-(RN2C-2)") (class "Default")
      (node (ref "RN2") (pin "6") (pinfunction "2_6") (pintype "passive"))
      (node (ref "RX") (pin "A") (pinfunction "A_A") (pintype "passive"))
    )
    (net (code "65") (name "Net-(RN2D-2)") (class "Default")
      (node (ref "RN2") (pin "5") (pinfunction "2_5") (pintype "passive"))
      (node (ref "TX") (pin "A") (pinfunction "A_A") (pintype "passive"))
    )
    (net (code "66") (name "Net-(RN4C-2)") (class "Default")
      (node (ref "ON") (pin "A") (pinfunction "A_A") (pintype "passive"))
      (node (ref "RN4") (pin "5") (pinfunction "2_5") (pintype "passive"))
      (node (ref "RN4") (pin "6") (pinfunction "2_6") (pintype "passive"))
    )
    (net (code "67") (name "Net-(U4-A2)") (class "Default")
      (node (ref "JP2") (pin "DI") (pinfunction "DI_DI") (pintype "bidirectional"))
      (node (ref "U4") (pin "3") (pinfunction "A2_3") (pintype "bidirectional"))
    )
    (net (code "68") (name "Net-(U4-A4)") (class "Default")
      (node (ref "JP2") (pin "DO") (pinfunction "DO_DO") (pintype "bidirectional"))
      (node (ref "U4") (pin "5") (pinfunction "A4_5") (pintype "bidirectional"))
    )
    (net (code "69") (name "RX") (class "Default")
      (node (ref "IOL") (pin "1") (pinfunction "1_1") (pintype "passive"))
      (node (ref "JP_MAX485") (pin "8") (pinfunction "8_8") (pintype "passive"))
      (node (ref "RN4") (pin "2") (pinfunction "1_2") (pintype "passive"))
      (node (ref "ZIC1") (pin "2") (pinfunction "(RXD)PD0_2") (pintype "bidirectional"))
    )
    (net (code "70") (name "SCK") (class "Default")
      (node (ref "ICSP") (pin "3") (pinfunction "3_3") (pintype "passive"))
      (node (ref "IOH") (pin "6") (pinfunction "6_6") (pintype "passive"))
      (node (ref "RN2") (pin "7") (pinfunction "2_7") (pintype "passive"))
      (node (ref "RN2") (pin "8") (pinfunction "2_8") (pintype "passive"))
      (node (ref "U4") (pin "11") (pinfunction "B3_11") (pintype "bidirectional"))
      (node (ref "ZIC1") (pin "19") (pinfunction "(SCK)PB5_19") (pintype "bidirectional"))
    )
    (net (code "71") (name "TX") (class "Default")
      (node (ref "IOL") (pin "2") (pinfunction "2_2") (pintype "passive"))
      (node (ref "JP_MAX485") (pin "2") (pinfunction "2_2") (pintype "passive"))
      (node (ref "RN4") (pin "1") (pinfunction "1_1") (pintype "passive"))
      (node (ref "ZIC1") (pin "3") (pinfunction "(TXD)PD1_3") (pintype "bidirectional"))
    )
    (net (code "72") (name "unconnected-(RN3B-1-Pad2)") (class "Default")
      (node (ref "RN3") (pin "2") (pinfunction "1_2") (pintype "passive"))
    )
    (net (code "73") (name "unconnected-(RN3B-2-Pad7)") (class "Default")
      (node (ref "RN3") (pin "7") (pinfunction "2_7") (pintype "passive"))
    )
    (net (code "74") (name "unconnected-(RN3C-1-Pad3)") (class "Default")
      (node (ref "RN3") (pin "3") (pinfunction "1_3") (pintype "passive"))
    )
    (net (code "75") (name "unconnected-(RN3C-2-Pad6)") (class "Default")
      (node (ref "RN3") (pin "6") (pinfunction "2_6") (pintype "passive"))
    )
    (net (code "76") (name "unconnected-(R_MAX1-Pad1)") (class "Default")
      (node (ref "R_MAX1") (pin "1") (pinfunction "1_1") (pintype "passive"))
    )
    (net (code "77") (name "unconnected-(R_MAX1-Pad2)") (class "Default")
      (node (ref "R_MAX1") (pin "2") (pinfunction "2_2") (pintype "passive"))
    )
    (net (code "78") (name "unconnected-(U1B-OUT-Pad7)") (class "Default")
      (node (ref "U1") (pin "7") (pinfunction "OUT_7") (pintype "output"))
    )
    (net (code "79") (name "unconnected-(U2-NC{slash}FB-Pad4)") (class "Default")
      (node (ref "U2") (pin "4") (pinfunction "NC/FB_4") (pintype "passive"))
    )
    (net (code "80") (name "unconnected-(U3-(AIN0{slash}INT1)PD1-Pad7)") (class "Default")
      (node (ref "U3") (pin "7") (pinfunction "(AIN0/INT1)PD1_7") (pintype "bidirectional"))
    )
    (net (code "81") (name "unconnected-(U3-(AIN2{slash}PCINT11)PC2-Pad5)") (class "Default")
      (node (ref "U3") (pin "5") (pinfunction "(AIN2/PCINT11)PC2_5") (pintype "bidirectional"))
    )
    (net (code "82") (name "unconnected-(U3-(INT4{slash}ICP1{slash}CLK0)PC7-Pad22)") (class "Default")
      (node (ref "U3") (pin "22") (pinfunction "(INT4/ICP1/CLK0)PC7_22") (pintype "bidirectional"))
    )
    (net (code "83") (name "unconnected-(U3-(OC0B{slash}INT0)PD0-Pad6)") (class "Default")
      (node (ref "U3") (pin "6") (pinfunction "(OC0B/INT0)PD0_6") (pintype "bidirectional"))
    )
    (net (code "84") (name "unconnected-(U3-(OC1A{slash}PCINT8)PC6-Pad23)") (class "Default")
      (node (ref "U3") (pin "23") (pinfunction "(OC1A/PCINT8)PC6_23") (pintype "bidirectional"))
    )
    (net (code "85") (name "unconnected-(U3-(PCINT5)PB5-Pad19)") (class "Default")
      (node (ref "U3") (pin "19") (pinfunction "(PCINT5)PB5_19") (pintype "bidirectional"))
    )
    (net (code "86") (name "unconnected-(U3-(PCINT6)PB6-Pad20)") (class "Default")
      (node (ref "U3") (pin "20") (pinfunction "(PCINT6)PB6_20") (pintype "bidirectional"))
    )
    (net (code "87") (name "unconnected-(U3-(PCINT7{slash}OC0A{slash}OC1C)PB7-Pad21)") (class "Default")
      (node (ref "U3") (pin "21") (pinfunction "(PCINT7/OC0A/OC1C)PB7_21") (pintype "bidirectional"))
    )
    (net (code "88") (name "unconnected-(U3-(PCINT9{slash}OC1B)PC5-Pad25)") (class "Default")
      (node (ref "U3") (pin "25") (pinfunction "(PCINT9/OC1B)PC5_25") (pintype "bidirectional"))
    )
    (net (code "89") (name "unconnected-(U3-(PCINT10)PC4-Pad26)") (class "Default")
      (node (ref "U3") (pin "26") (pinfunction "(PCINT10)PC4_26") (pintype "bidirectional"))
    )
    (net (code "90") (name "unconnected-(U3-(RTS{slash}AIN5{slash}INT6)PD6-Pad12)") (class "Default")
      (node (ref "U3") (pin "12") (pinfunction "(RTS/AIN5/INT6)PD6_12") (pintype "bidirectional"))
    )
    (net (code "91") (name "unconnected-(U3-(SS{slash}PCINT0)PB0-Pad14)") (class "Default")
      (node (ref "U3") (pin "14") (pinfunction "(SS/PCINT0)PB0_14") (pintype "bidirectional"))
    )
    (net (code "92") (name "unconnected-(U3-(T1{slash}PCINT4)PB4-Pad18)") (class "Default")
      (node (ref "U3") (pin "18") (pinfunction "(T1/PCINT4)PB4_18") (pintype "bidirectional"))
    )
  )
)
